# Schematic.net
KiCad netlist of a schematic drawn in Altium Designer
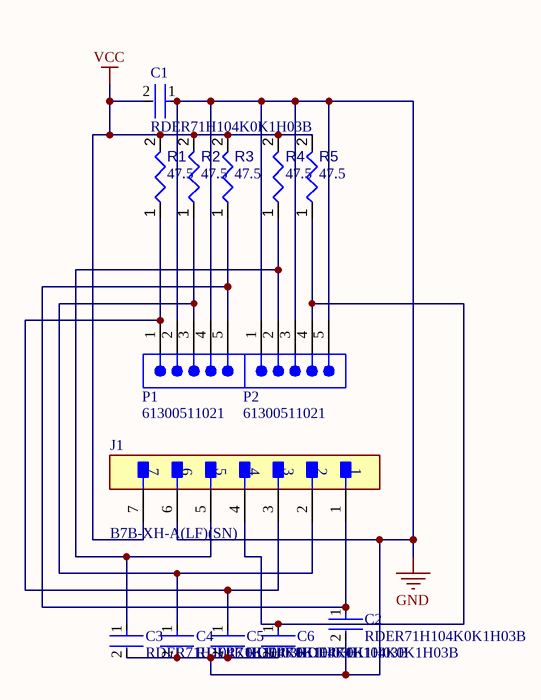
[diagram p0: Schematic.SchDoc]

(export (version "E")
  (design (tool "Eeschema 10.0.6"))
  (components
    (comp (ref "C1")
      (value "RDER71H104K0K1H03B")
      (footprint "FP-RDE0M1-MFG")
      (description "Ceramic Capacitor 100nF ±10% 50V X7R Radial")
      (fields (field (name "TOLERANCE") "10%"))
      (libsource (lib "Altium Content Vault") (part "b4654b650e69147ec39a6b967a45e02"))
    )
    (comp (ref "C2")
      (value "RDER71H104K0K1H03B")
      (footprint "FP-RDE0M1-MFG")
      (description "Ceramic Capacitor 100nF ±10% 50V X7R Radial")
      (fields (field (name "TOLERANCE") "10%"))
      (libsource (lib "Altium Content Vault") (part "b4654b650e69147ec39a6b967a45e02"))
    )
    (comp (ref "C3")
      (value "RDER71H104K0K1H03B")
      (footprint "FP-RDE0M1-MFG")
      (description "Ceramic Capacitor 100nF ±10% 50V X7R Radial")
      (fields (field (name "TOLERANCE") "10%"))
      (libsource (lib "Altium Content Vault") (part "b4654b650e69147ec39a6b967a45e02"))
    )
    (comp (ref "C4")
      (value "RDER71H104K0K1H03B")
      (footprint "FP-RDE0M1-MFG")
      (description "Ceramic Capacitor 100nF ±10% 50V X7R Radial")
      (fields (field (name "TOLERANCE") "10%"))
      (libsource (lib "Altium Content Vault") (part "b4654b650e69147ec39a6b967a45e02"))
    )
    (comp (ref "C5")
      (value "RDER71H104K0K1H03B")
      (footprint "FP-RDE0M1-MFG")
      (description "Ceramic Capacitor 100nF ±10% 50V X7R Radial")
      (fields (field (name "TOLERANCE") "10%"))
      (libsource (lib "Altium Content Vault") (part "b4654b650e69147ec39a6b967a45e02"))
    )
    (comp (ref "C6")
      (value "RDER71H104K0K1H03B")
      (footprint "FP-RDE0M1-MFG")
      (description "Ceramic Capacitor 100nF ±10% 50V X7R Radial")
      (fields (field (name "TOLERANCE") "10%"))
      (libsource (lib "Altium Content Vault") (part "b4654b650e69147ec39a6b967a45e02"))
    )
    (comp (ref "J1")
      (value "B7B-XH-A(LF)(SN)")
      (footprint "FP-B7B-XH-A_LF_SN-MFG")
      (description "CONN HEADER VERT 7POS 2.5MM")
      (libsource (lib "Altium Content Vault") (part "5bcee6b94e1fee4be3f4cc3a650a442"))
    )
    (comp (ref "P1")
      (value "61300511021")
      (footprint "61300511021")
      (libsource (lib "Altium Content Vault") (part "Header_Male_1R_05P"))
    )
    (comp (ref "P2")
      (value "61300511021")
      (footprint "61300511021")
      (libsource (lib "Altium Content Vault") (part "Header_Male_1R_05P"))
    )
    (comp (ref "R1")
      (value "47.5")
      (footprint "RESA60-630X240")
      (description "Axial Resistor, 47.5 Ohm, +/- 1%, 0.25 W, -55 to 155 degC, 2-Pin THD, RoHS, Bulk")
      (fields (field (name "MANUFACTURER") "Yageo") (field (name "TOLERANCE") "1%"))
      (libsource (lib "ahmed waleed") (part "RES-2"))
    )
    (comp (ref "R2")
      (value "47.5")
      (footprint "RESA60-630X240")
      (description "Axial Resistor, 47.5 Ohm, +/- 1%, 0.25 W, -55 to 155 degC, 2-Pin THD, RoHS, Bulk")
      (fields (field (name "MANUFACTURER") "Yageo") (field (name "TOLERANCE") "1%"))
      (libsource (lib "ahmed waleed") (part "RES-2"))
    )
    (comp (ref "R3")
      (value "47.5")
      (footprint "RESA60-630X240")
      (description "Axial Resistor, 47.5 Ohm, +/- 1%, 0.25 W, -55 to 155 degC, 2-Pin THD, RoHS, Bulk")
      (fields (field (name "MANUFACTURER") "Yageo") (field (name "TOLERANCE") "1%"))
      (libsource (lib "ahmed waleed") (part "RES-2"))
    )
    (comp (ref "R4")
      (value "47.5")
      (footprint "RESA60-630X240")
      (description "Axial Resistor, 47.5 Ohm, +/- 1%, 0.25 W, -55 to 155 degC, 2-Pin THD, RoHS, Bulk")
      (fields (field (name "MANUFACTURER") "Yageo") (field (name "TOLERANCE") "1%"))
      (libsource (lib "ahmed waleed") (part "RES-2"))
    )
    (comp (ref "R5")
      (value "47.5")
      (footprint "RESA60-630X240")
      (description "Axial Resistor, 47.5 Ohm, +/- 1%, 0.25 W, -55 to 155 degC, 2-Pin THD, RoHS, Bulk")
      (fields (field (name "MANUFACTURER") "Yageo") (field (name "TOLERANCE") "1%"))
      (libsource (lib "ahmed waleed") (part "RES-2"))
    )
  )
  (nets
    (net (code "1") (name "GND") (class "Default")
      (node (ref "C1") (pin "1") (pinfunction "1_1") (pintype "passive"))
      (node (ref "C2") (pin "2") (pinfunction "2_2") (pintype "passive"))
      (node (ref "C3") (pin "2") (pinfunction "2_2") (pintype "passive"))
      (node (ref "C4") (pin "2") (pinfunction "2_2") (pintype "passive"))
      (node (ref "C5") (pin "2") (pinfunction "2_2") (pintype "passive"))
      (node (ref "C6") (pin "2") (pinfunction "2_2") (pintype "passive"))
      (node (ref "J1") (pin "6") (pinfunction "6_6") (pintype "passive"))
      (node (ref "P1") (pin "2") (pinfunction "2_2") (pintype "passive"))
      (node (ref "P1") (pin "4") (pinfunction "4_4") (pintype "passive"))
      (node (ref "P2") (pin "1") (pinfunction "1_1") (pintype "passive"))
      (node (ref "P2") (pin "3") (pinfunction "3_3") (pintype "passive"))
      (node (ref "P2") (pin "5") (pinfunction "5_5") (pintype "passive"))
    )
    (net (code "2") (name "Net-(C2-Pad1)") (class "Default")
      (node (ref "C2") (pin "1") (pinfunction "1_1") (pintype "passive"))
      (node (ref "J1") (pin "1") (pinfunction "1_1") (pintype "passive"))
      (node (ref "P1") (pin "5") (pinfunction "5_5") (pintype "passive"))
      (node (ref "R3") (pin "1") (pinfunction "1_1") (pintype "passive"))
    )
    (net (code "3") (name "Net-(C3-Pad1)") (class "Default")
      (node (ref "C3") (pin "1") (pinfunction "1_1") (pintype "passive"))
      (node (ref "J1") (pin "5") (pinfunction "5_5") (pintype "passive"))
      (node (ref "P2") (pin "2") (pinfunction "2_2") (pintype "passive"))
      (node (ref "R4") (pin "1") (pinfunction "1_1") (pintype "passive"))
    )
    (net (code "4") (name "Net-(C4-Pad1)") (class "Default")
      (node (ref "C4") (pin "1") (pinfunction "1_1") (pintype "passive"))
      (node (ref "J1") (pin "2") (pinfunction "2_2") (pintype "passive"))
      (node (ref "P1") (pin "3") (pinfunction "3_3") (pintype "passive"))
      (node (ref "R2") (pin "1") (pinfunction "1_1") (pintype "passive"))
    )
    (net (code "5") (name "Net-(C5-Pad1)") (class "Default")
      (node (ref "C5") (pin "1") (pinfunction "1_1") (pintype "passive"))
      (node (ref "J1") (pin "3") (pinfunction "3_3") (pintype "passive"))
      (node (ref "P1") (pin "1") (pinfunction "1_1") (pintype "passive"))
      (node (ref "R1") (pin "1") (pinfunction "1_1") (pintype "passive"))
    )
    (net (code "6") (name "Net-(C6-Pad1)") (class "Default")
      (node (ref "C6") (pin "1") (pinfunction "1_1") (pintype "passive"))
      (node (ref "J1") (pin "4") (pinfunction "4_4") (pintype "passive"))
      (node (ref "P2") (pin "4") (pinfunction "4_4") (pintype "passive"))
      (node (ref "R5") (pin "1") (pinfunction "1_1") (pintype "passive"))
    )
    (net (code "7") (name "VCC") (class "Default")
      (node (ref "C1") (pin "2") (pinfunction "2_2") (pintype "passive"))
      (node (ref "J1") (pin "7") (pinfunction "7_7") (pintype "passive"))
      (node (ref "R1") (pin "2") (pinfunction "2_2") (pintype "passive"))
      (node (ref "R2") (pin "2") (pinfunction "2_2") (pintype "passive"))
      (node (ref "R3") (pin "2") (pinfunction "2_2") (pintype "passive"))
      (node (ref "R4") (pin "2") (pinfunction "2_2") (pintype "passive"))
      (node (ref "R5") (pin "2") (pinfunction "2_2") (pintype "passive"))
    )
  )
)
